# Pure_SH.net
KiCad netlist of a schematic drawn in EAGLE
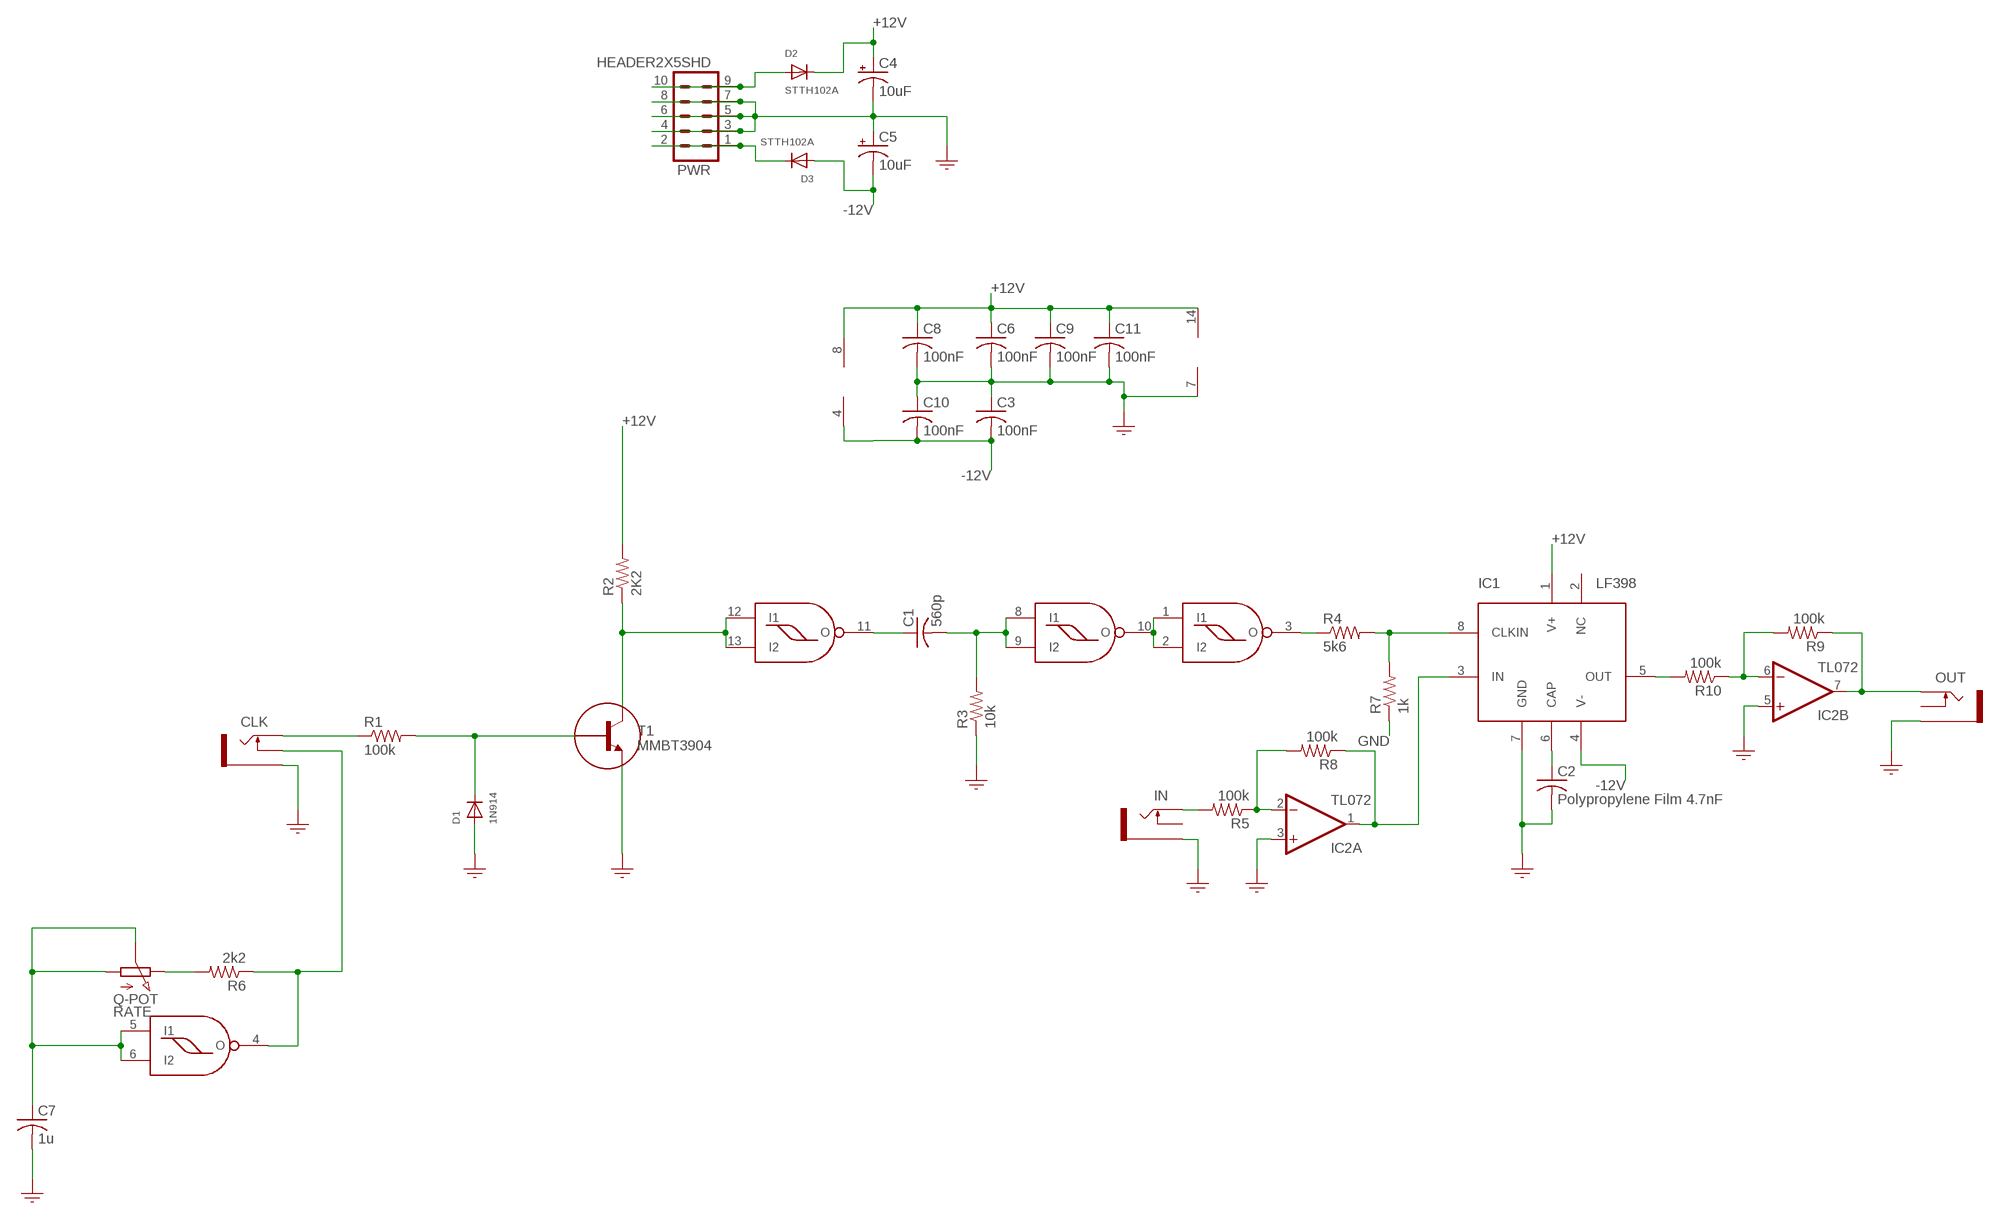
[diagram p0: schematic, sheet 1]

(export (version "E")
  (design (tool "Eeschema 10.0.6"))
  (components
    (comp (ref "C1")
      (value "560p")
      (footprint "eagle-import:C0805")
      (libsource (lib "eagle-import") (part "CAPACITOR-USC0805"))
    )
    (comp (ref "C2")
      (value "Polypropylene Film 4.7nF")
      (footprint "eagle-import:C050-045X075")
      (libsource (lib "eagle-import") (part "CAPACITOR-USC050-045X075"))
    )
    (comp (ref "C3")
      (value "100nF")
      (footprint "eagle-import:C0805")
      (libsource (lib "eagle-import") (part "CAPACITOR-USC0805"))
    )
    (comp (ref "C4")
      (value "10uF")
      (footprint "eagle-import:153CLV-0505")
      (libsource (lib "eagle-import") (part "CAPACITOR_POL-US153CLV-0505"))
    )
    (comp (ref "C5")
      (value "10uF")
      (footprint "eagle-import:153CLV-0505")
      (libsource (lib "eagle-import") (part "CAPACITOR_POL-US153CLV-0505"))
    )
    (comp (ref "C6")
      (value "100nF")
      (footprint "eagle-import:C0805")
      (libsource (lib "eagle-import") (part "CAPACITOR-USC0805"))
    )
    (comp (ref "C7")
      (value "1u")
      (footprint "eagle-import:C0805")
      (libsource (lib "eagle-import") (part "CAPACITOR-USC0805"))
    )
    (comp (ref "C8")
      (value "100nF")
      (footprint "eagle-import:C0805")
      (libsource (lib "eagle-import") (part "CAPACITOR-USC0805"))
    )
    (comp (ref "C9")
      (value "100nF")
      (footprint "eagle-import:C0805")
      (libsource (lib "eagle-import") (part "CAPACITOR-USC0805"))
    )
    (comp (ref "C10")
      (value "100nF")
      (footprint "eagle-import:C0805")
      (libsource (lib "eagle-import") (part "CAPACITOR-USC0805"))
    )
    (comp (ref "C11")
      (value "100nF")
      (footprint "eagle-import:C0805")
      (libsource (lib "eagle-import") (part "CAPACITOR-USC0805"))
    )
    (comp (ref "CLK")
      (value "PJ301M-12")
      (footprint "eagle-import:PJ301M-12")
      (libsource (lib "eagle-import") (part "SOCKET_MONO_3.5MMPJ301M-12"))
    )
    (comp (ref "D1")
      (value "1N914")
      (footprint "eagle-import:DO-41")
      (libsource (lib "eagle-import") (part "DIODEDO-41"))
    )
    (comp (ref "D2")
      (value "STTH102A")
      (footprint "eagle-import:SMADIODE")
      (libsource (lib "eagle-import") (part "DIODESMA"))
    )
    (comp (ref "D3")
      (value "STTH102A")
      (footprint "eagle-import:SMADIODE")
      (libsource (lib "eagle-import") (part "DIODESMA"))
    )
    (comp (ref "IC1")
      (value "LF398")
      (footprint "eagle-import:SOIC--8")
      (libsource (lib "eagle-import") (part "SAMPLE_HOLD_LF398"))
    )
    (comp (ref "IC2")
      (value "TL072")
      (footprint "eagle-import:SO08")
      (libsource (lib "eagle-import") (part "OPAMP_DUALD"))
    )
    (comp (ref "IC3")
      (value "cd4093")
      (footprint "eagle-import:SOIC14")
      (libsource (lib "eagle-import") (part "SCHMITT_TRIG_QUAD"))
    )
    (comp (ref "IN")
      (value "PJ301M-12")
      (footprint "eagle-import:PJ301M-12")
      (libsource (lib "eagle-import") (part "SOCKET_MONO_3.5MMPJ301M-12"))
    )
    (comp (ref "OUT")
      (value "PJ301M-12")
      (footprint "eagle-import:PJ301M-12")
      (libsource (lib "eagle-import") (part "SOCKET_MONO_3.5MMPJ301M-12"))
    )
    (comp (ref "PWR")
      (value "HEADER2X5SHD")
      (footprint "eagle-import:2X5-SHROUDED")
      (libsource (lib "eagle-import") (part "HEADER2X5SHD"))
    )
    (comp (ref "R1")
      (value "100k")
      (footprint "eagle-import:R0805")
      (libsource (lib "eagle-import") (part "RESISTOR_USR0805"))
    )
    (comp (ref "R2")
      (value "2K2")
      (footprint "eagle-import:R0805")
      (libsource (lib "eagle-import") (part "RESISTOR_USR0805"))
    )
    (comp (ref "R3")
      (value "10k")
      (footprint "eagle-import:R0805")
      (libsource (lib "eagle-import") (part "RESISTOR_USR0805"))
    )
    (comp (ref "R4")
      (value "5k6")
      (footprint "eagle-import:R0805")
      (libsource (lib "eagle-import") (part "RESISTOR_USR0805"))
    )
    (comp (ref "R5")
      (value "100k")
      (footprint "eagle-import:R0805")
      (libsource (lib "eagle-import") (part "RESISTOR_USR0805"))
    )
    (comp (ref "R6")
      (value "2k2")
      (footprint "eagle-import:R0805")
      (libsource (lib "eagle-import") (part "RESISTOR_USR0805"))
    )
    (comp (ref "R7")
      (value "1k")
      (footprint "eagle-import:R0805")
      (libsource (lib "eagle-import") (part "RESISTOR_USR0805"))
    )
    (comp (ref "R8")
      (value "100k")
      (footprint "eagle-import:R0805")
      (libsource (lib "eagle-import") (part "RESISTOR_USR0805"))
    )
    (comp (ref "R9")
      (value "100k")
      (footprint "eagle-import:R0805")
      (libsource (lib "eagle-import") (part "RESISTOR_USR0805"))
    )
    (comp (ref "R10")
      (value "100k")
      (footprint "eagle-import:R0805")
      (libsource (lib "eagle-import") (part "RESISTOR_USR0805"))
    )
    (comp (ref "RATE")
      (value "Q-POT")
      (footprint "eagle-import:POTENTIOMETER_9MM")
      (libsource (lib "eagle-import") (part "RESISTOR_VARIABLE9MM_POT"))
    )
    (comp (ref "T1")
      (value "MMBT3904")
      (footprint "eagle-import:SOT23")
      (libsource (lib "eagle-import") (part "TRANSISTOR_NPNSOT23"))
    )
  )
  (nets
    (net (code "1") (name "/+12V") (class "Default")
      (node (ref "C11") (pin "1") (pinfunction "1_1") (pintype "passive"))
      (node (ref "C4") (pin "+") (pinfunction "+_+") (pintype "passive"))
      (node (ref "C6") (pin "1") (pinfunction "1_1") (pintype "passive"))
      (node (ref "C8") (pin "1") (pinfunction "1_1") (pintype "passive"))
      (node (ref "C9") (pin "1") (pinfunction "1_1") (pintype "passive"))
      (node (ref "D2") (pin "C") (pinfunction "C_C") (pintype "passive"))
      (node (ref "IC1") (pin "1") (pinfunction "V+_1") (pintype "bidirectional"))
      (node (ref "IC2") (pin "8") (pinfunction "V+_8") (pintype "power_in"))
      (node (ref "IC3") (pin "14") (pinfunction "V+_14") (pintype "power_in"))
      (node (ref "R2") (pin "2") (pinfunction "2_2") (pintype "passive"))
    )
    (net (code "2") (name "/-12V") (class "Default")
      (node (ref "C10") (pin "2") (pinfunction "2_2") (pintype "passive"))
      (node (ref "C3") (pin "2") (pinfunction "2_2") (pintype "passive"))
      (node (ref "C5") (pin "-") (pinfunction "-_-") (pintype "passive"))
      (node (ref "D3") (pin "A") (pinfunction "A_A") (pintype "passive"))
      (node (ref "IC1") (pin "4") (pinfunction "V-_4") (pintype "bidirectional"))
      (node (ref "IC2") (pin "4") (pinfunction "V-_4") (pintype "power_in"))
    )
    (net (code "3") (name "GND") (class "Default")
      (node (ref "C10") (pin "1") (pinfunction "1_1") (pintype "passive"))
      (node (ref "C11") (pin "2") (pinfunction "2_2") (pintype "passive"))
      (node (ref "C2") (pin "2") (pinfunction "2_2") (pintype "passive"))
      (node (ref "C3") (pin "1") (pinfunction "1_1") (pintype "passive"))
      (node (ref "C4") (pin "-") (pinfunction "-_-") (pintype "passive"))
      (node (ref "C5") (pin "+") (pinfunction "+_+") (pintype "passive"))
      (node (ref "C6") (pin "2") (pinfunction "2_2") (pintype "passive"))
      (node (ref "C7") (pin "2") (pinfunction "2_2") (pintype "passive"))
      (node (ref "C8") (pin "2") (pinfunction "2_2") (pintype "passive"))
      (node (ref "C9") (pin "2") (pinfunction "2_2") (pintype "passive"))
      (node (ref "CLK") (pin "GND") (pinfunction "SLEEVE_GND") (pintype "passive"))
      (node (ref "D1") (pin "A") (pinfunction "A_A") (pintype "passive"))
      (node (ref "IC1") (pin "7") (pinfunction "GND_7") (pintype "bidirectional"))
      (node (ref "IC2") (pin "3") (pinfunction "+IN_3") (pintype "input"))
      (node (ref "IC2") (pin "5") (pinfunction "+IN_5") (pintype "input"))
      (node (ref "IC3") (pin "7") (pinfunction "V-_7") (pintype "power_in"))
      (node (ref "IN") (pin "GND") (pinfunction "SLEEVE_GND") (pintype "passive"))
      (node (ref "OUT") (pin "GND") (pinfunction "SLEEVE_GND") (pintype "passive"))
      (node (ref "PWR") (pin "3") (pinfunction "3_3") (pintype "passive"))
      (node (ref "PWR") (pin "4") (pinfunction "4_4") (pintype "passive"))
      (node (ref "PWR") (pin "5") (pinfunction "5_5") (pintype "passive"))
      (node (ref "PWR") (pin "6") (pinfunction "6_6") (pintype "passive"))
      (node (ref "PWR") (pin "7") (pinfunction "7_7") (pintype "passive"))
      (node (ref "PWR") (pin "8") (pinfunction "8_8") (pintype "passive"))
      (node (ref "R3") (pin "1") (pinfunction "1_1") (pintype "passive"))
      (node (ref "R7") (pin "1") (pinfunction "1_1") (pintype "passive"))
      (node (ref "T1") (pin "2") (pinfunction "E_2") (pintype "passive"))
    )
    (net (code "4") (name "Net-(CLK-PadTIP)") (class "Default")
      (node (ref "CLK") (pin "TIP") (pinfunction "TIP_TIP") (pintype "passive"))
      (node (ref "R1") (pin "1") (pinfunction "1_1") (pintype "passive"))
    )
    (net (code "5") (name "Net-(CLK-SWITCH)") (class "Default")
      (node (ref "CLK") (pin "NORM") (pinfunction "SWITCH_NORM") (pintype "passive"))
      (node (ref "IC3") (pin "4") (pinfunction "O_4") (pintype "bidirectional"))
      (node (ref "R6") (pin "1") (pinfunction "1_1") (pintype "passive"))
    )
    (net (code "6") (name "Net-(D2-PadA)") (class "Default")
      (node (ref "D2") (pin "A") (pinfunction "A_A") (pintype "passive"))
      (node (ref "PWR") (pin "10") (pinfunction "10_10") (pintype "passive"))
      (node (ref "PWR") (pin "9") (pinfunction "9_9") (pintype "passive"))
    )
    (net (code "7") (name "Net-(D3-PadC)") (class "Default")
      (node (ref "D3") (pin "C") (pinfunction "C_C") (pintype "passive"))
      (node (ref "PWR") (pin "1") (pinfunction "1_1") (pintype "passive"))
      (node (ref "PWR") (pin "2") (pinfunction "2_2") (pintype "passive"))
    )
    (net (code "8") (name "Net-(IC1-CAP)") (class "Default")
      (node (ref "C2") (pin "1") (pinfunction "1_1") (pintype "passive"))
      (node (ref "IC1") (pin "6") (pinfunction "CAP_6") (pintype "bidirectional"))
    )
    (net (code "9") (name "Net-(IC1-CLKIN)") (class "Default")
      (node (ref "IC1") (pin "8") (pinfunction "CLKIN_8") (pintype "bidirectional"))
      (node (ref "R4") (pin "2") (pinfunction "2_2") (pintype "passive"))
      (node (ref "R7") (pin "2") (pinfunction "2_2") (pintype "passive"))
    )
    (net (code "10") (name "Net-(IC1-IN)") (class "Default")
      (node (ref "IC1") (pin "3") (pinfunction "IN_3") (pintype "bidirectional"))
      (node (ref "IC2") (pin "1") (pinfunction "OUT_1") (pintype "output"))
      (node (ref "R8") (pin "1") (pinfunction "1_1") (pintype "passive"))
    )
    (net (code "11") (name "Net-(IC1-OUT)") (class "Default")
      (node (ref "IC1") (pin "5") (pinfunction "OUT_5") (pintype "bidirectional"))
      (node (ref "R10") (pin "2") (pinfunction "2_2") (pintype "passive"))
    )
    (net (code "12") (name "Net-(IC2A--IN)") (class "Default")
      (node (ref "IC2") (pin "2") (pinfunction "-IN_2") (pintype "input"))
      (node (ref "R5") (pin "1") (pinfunction "1_1") (pintype "passive"))
      (node (ref "R8") (pin "2") (pinfunction "2_2") (pintype "passive"))
    )
    (net (code "13") (name "Net-(IC2B--IN)") (class "Default")
      (node (ref "IC2") (pin "6") (pinfunction "-IN_6") (pintype "input"))
      (node (ref "R10") (pin "1") (pinfunction "1_1") (pintype "passive"))
      (node (ref "R9") (pin "2") (pinfunction "2_2") (pintype "passive"))
    )
    (net (code "14") (name "Net-(IC2B-OUT)") (class "Default")
      (node (ref "IC2") (pin "7") (pinfunction "OUT_7") (pintype "output"))
      (node (ref "OUT") (pin "TIP") (pinfunction "TIP_TIP") (pintype "passive"))
      (node (ref "R9") (pin "1") (pinfunction "1_1") (pintype "passive"))
    )
    (net (code "15") (name "Net-(IC3B-I1)") (class "Default")
      (node (ref "IC3") (pin "1") (pinfunction "I1_1") (pintype "bidirectional"))
      (node (ref "IC3") (pin "10") (pinfunction "O_10") (pintype "bidirectional"))
      (node (ref "IC3") (pin "2") (pinfunction "I2_2") (pintype "bidirectional"))
    )
    (net (code "16") (name "Net-(IC3B-O)") (class "Default")
      (node (ref "IC3") (pin "3") (pinfunction "O_3") (pintype "bidirectional"))
      (node (ref "R4") (pin "1") (pinfunction "1_1") (pintype "passive"))
    )
    (net (code "17") (name "Net-(IC3C-I1)") (class "Default")
      (node (ref "C7") (pin "1") (pinfunction "1_1") (pintype "passive"))
      (node (ref "IC3") (pin "5") (pinfunction "I1_5") (pintype "bidirectional"))
      (node (ref "IC3") (pin "6") (pinfunction "I2_6") (pintype "bidirectional"))
      (node (ref "RATE") (pin "P$1") (pinfunction "1_P$1") (pintype "passive"))
      (node (ref "RATE") (pin "P$2") (pinfunction "2_P$2") (pintype "passive"))
    )
    (net (code "18") (name "Net-(IC3D-I1)") (class "Default")
      (node (ref "C1") (pin "2") (pinfunction "2_2") (pintype "passive"))
      (node (ref "IC3") (pin "8") (pinfunction "I1_8") (pintype "bidirectional"))
      (node (ref "IC3") (pin "9") (pinfunction "I2_9") (pintype "bidirectional"))
      (node (ref "R3") (pin "2") (pinfunction "2_2") (pintype "passive"))
    )
    (net (code "19") (name "Net-(IC3E-I1)") (class "Default")
      (node (ref "IC3") (pin "12") (pinfunction "I1_12") (pintype "bidirectional"))
      (node (ref "IC3") (pin "13") (pinfunction "I2_13") (pintype "bidirectional"))
      (node (ref "R2") (pin "1") (pinfunction "1_1") (pintype "passive"))
      (node (ref "T1") (pin "3") (pinfunction "C_3") (pintype "passive"))
    )
    (net (code "20") (name "Net-(IC3E-O)") (class "Default")
      (node (ref "C1") (pin "1") (pinfunction "1_1") (pintype "passive"))
      (node (ref "IC3") (pin "11") (pinfunction "O_11") (pintype "bidirectional"))
    )
    (net (code "21") (name "Net-(IN-PadTIP)") (class "Default")
      (node (ref "IN") (pin "TIP") (pinfunction "TIP_TIP") (pintype "passive"))
      (node (ref "R5") (pin "2") (pinfunction "2_2") (pintype "passive"))
    )
    (net (code "22") (name "Net-(RATE-3)") (class "Default")
      (node (ref "R6") (pin "2") (pinfunction "2_2") (pintype "passive"))
      (node (ref "RATE") (pin "P$3") (pinfunction "3_P$3") (pintype "passive"))
    )
    (net (code "23") (name "Net-(T1-B)") (class "Default")
      (node (ref "D1") (pin "C") (pinfunction "C_C") (pintype "passive"))
      (node (ref "R1") (pin "2") (pinfunction "2_2") (pintype "passive"))
      (node (ref "T1") (pin "1") (pinfunction "B_1") (pintype "passive"))
    )
    (net (code "24") (name "unconnected-(IC1-NC-Pad2)") (class "Default")
      (node (ref "IC1") (pin "2") (pinfunction "NC_2") (pintype "bidirectional"))
    )
    (net (code "25") (name "unconnected-(IN-SWITCH-PadNORM)") (class "Default")
      (node (ref "IN") (pin "NORM") (pinfunction "SWITCH_NORM") (pintype "passive"))
    )
    (net (code "26") (name "unconnected-(OUT-SWITCH-PadNORM)") (class "Default")
      (node (ref "OUT") (pin "NORM") (pinfunction "SWITCH_NORM") (pintype "passive"))
    )
  )
)
